# 1-Schematic_Tutorial_PJ.net
KiCad netlist of a schematic drawn in EasyEDA
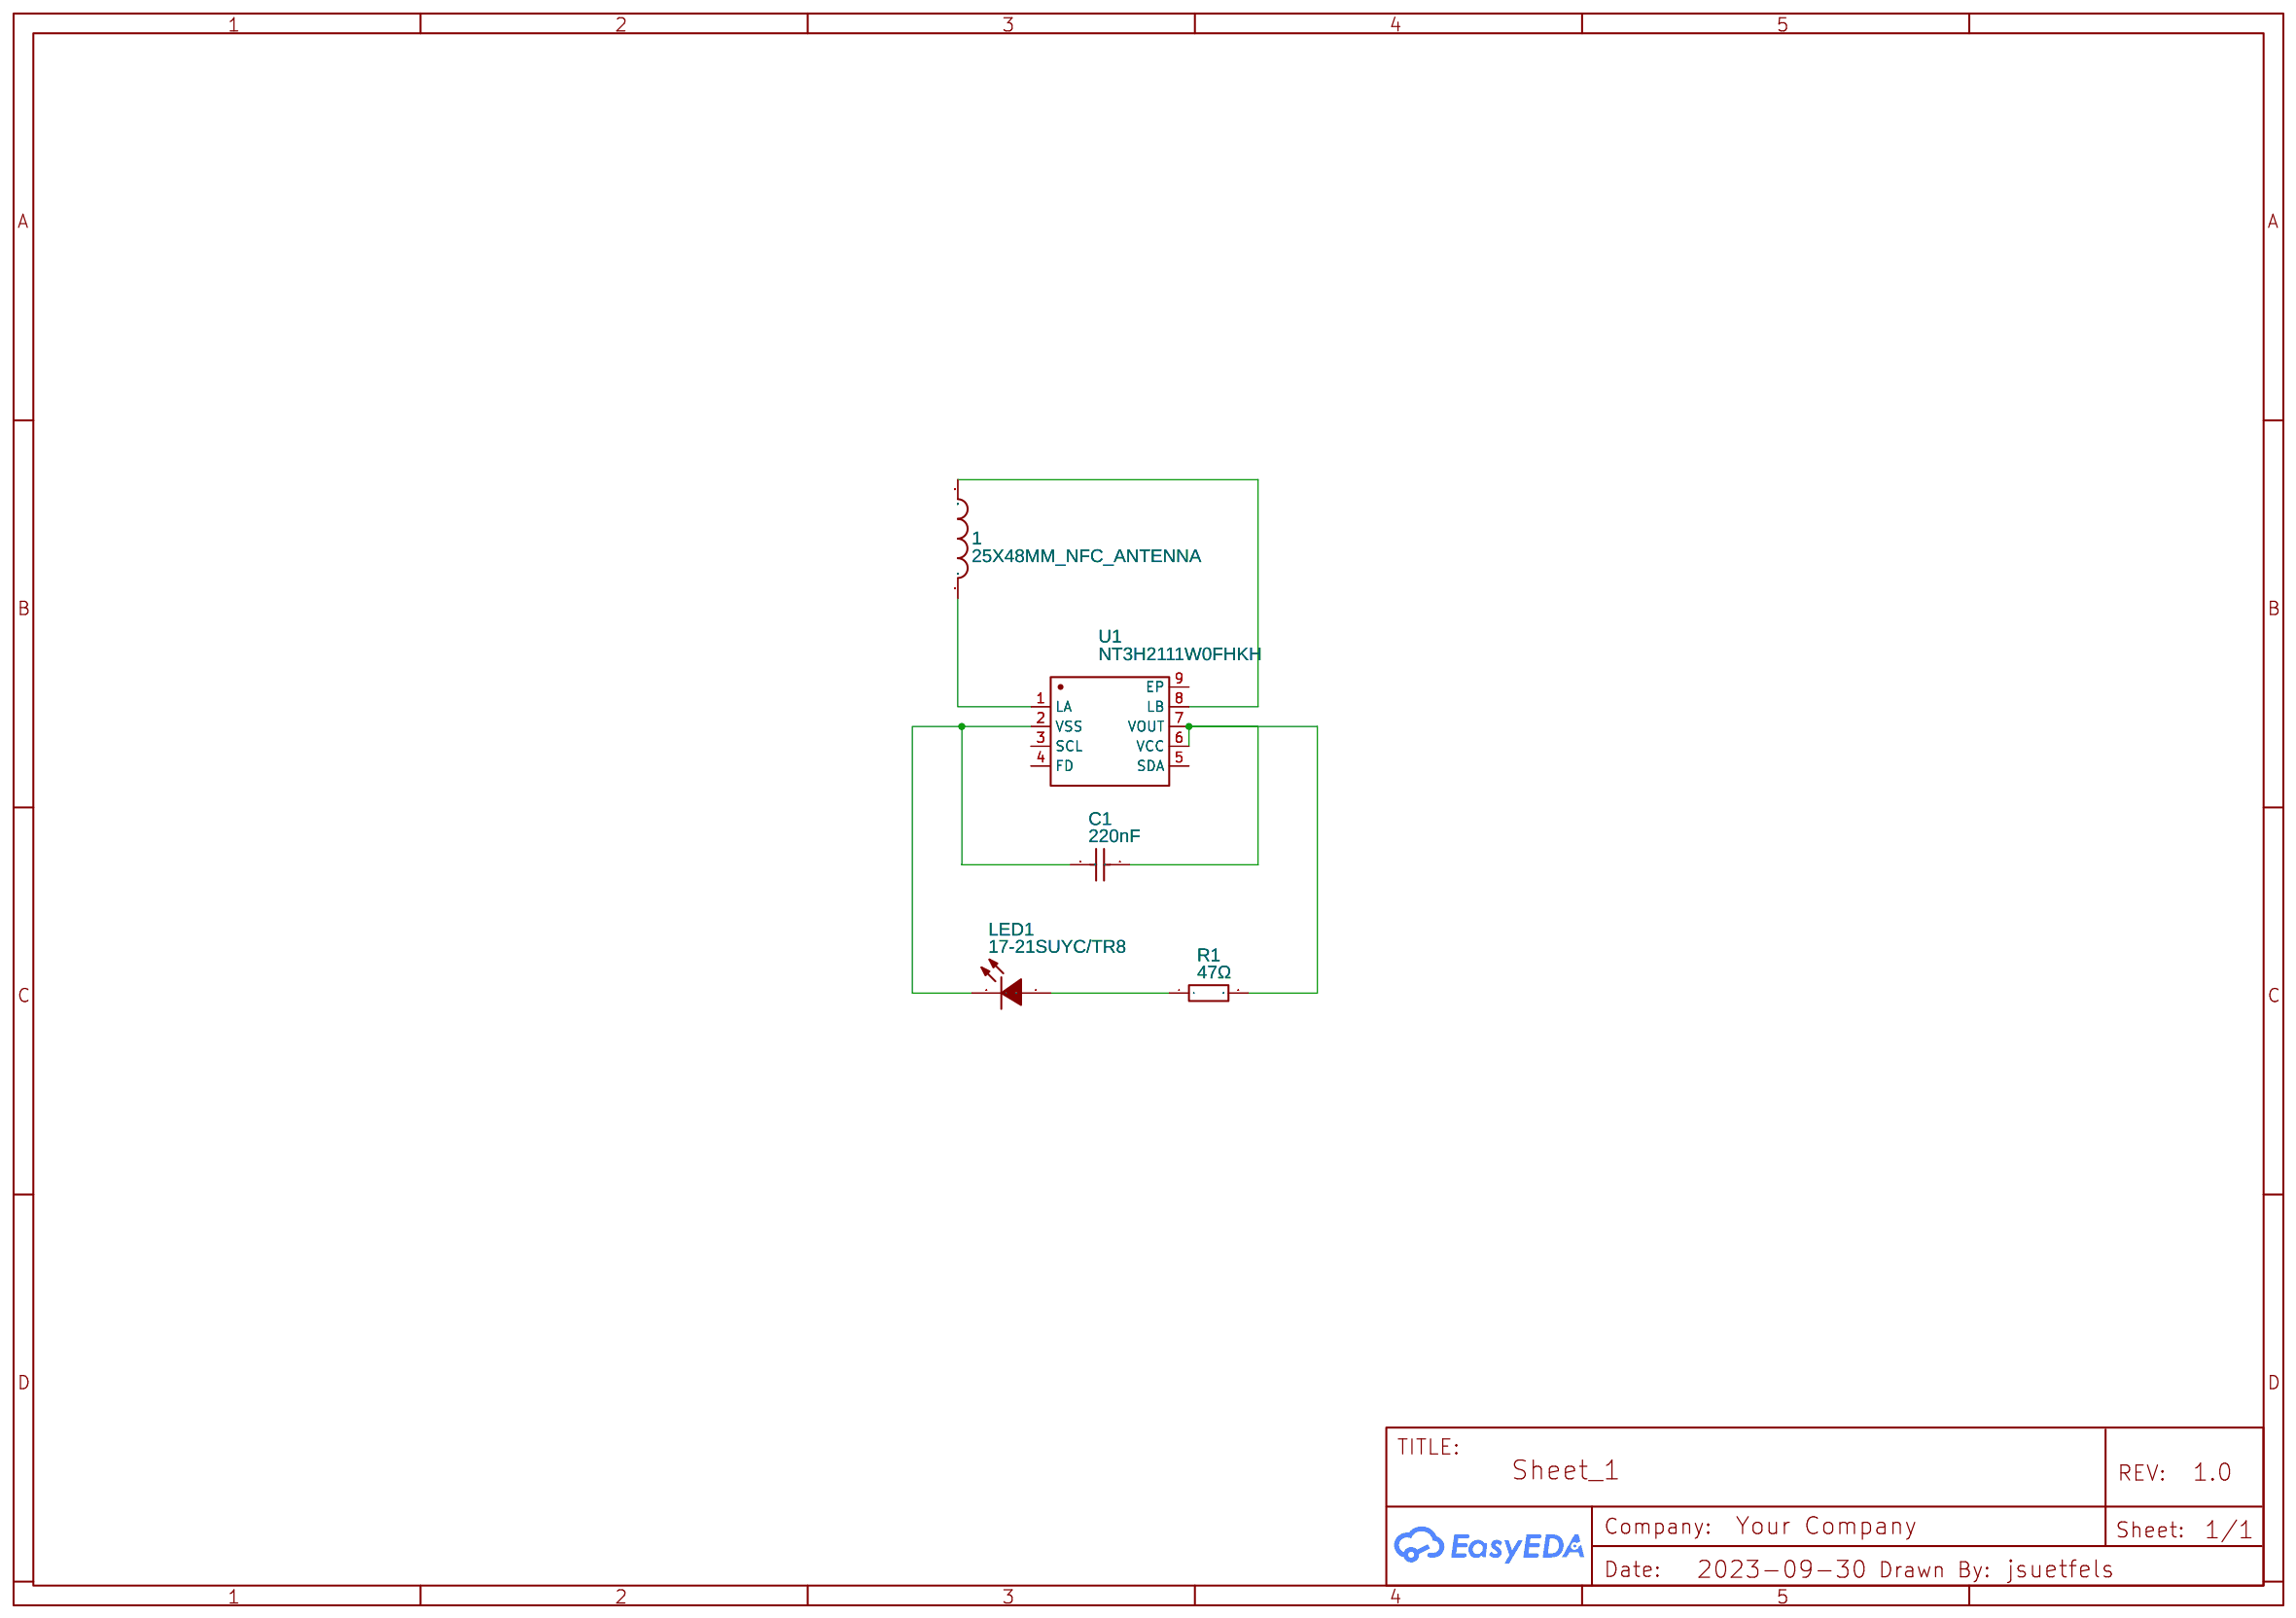
[diagram p0: schematic sheet]

(export (version "E")
  (design (tool "Eeschema 10.0.6"))
  (components
    (comp (ref "1") (value "25X48MM_NFC_ANTENNA") (libsource (lib "") (part "25X48MM_NFC_ANTENNA")))
    (comp (ref "C1")
      (value "220nF")
      (fields
        (field (name "Manufacturer Part") "CL10B224KA8NNNC")
        (field (name "Manufacturer") "SAMSUNG(三星)")
      )
      (libsource (lib "") (part "CL10B224KA8NNNC"))
    )
    (comp (ref "LED1")
      (value "17-21SUYC/TR8")
      (fields (field (name "Manufacturer Part") "KT-0805黄灯") (field (name "Manufacturer") "KENTO"))
      (libsource (lib "") (part "17-21SUYC/TR8"))
    )
    (comp (ref "R1")
      (value "47Ω")
      (fields
        (field (name "Manufacturer Part") "0603WAF470JT5E")
        (field (name "Manufacturer") "UNI-ROYAL(厚声)")
      )
      (libsource (lib "") (part "0603WAF470JT5E"))
    )
    (comp (ref "U1")
      (value "NT3H2111W0FHKH")
      (fields (field (name "Manufacturer") "NXP(恩智浦)"))
      (libsource (lib "") (part "NT3H2111W0FHKH"))
    )
  )
  (nets
    (net (code "1") (name "Net-(LED1-+)") (class "Default")
      (node (ref "LED1") (pin "1") (pinfunction "+_1") (pintype "unspecified"))
      (node (ref "R1") (pin "1") (pinfunction "1_1") (pintype "input"))
    )
    (net (code "2") (name "Net-(LED1--)") (class "Default")
      (node (ref "C1") (pin "1") (pinfunction "1_1") (pintype "input"))
      (node (ref "LED1") (pin "2") (pinfunction "-_2") (pintype "unspecified"))
      (node (ref "U1") (pin "2") (pinfunction "VSS_2") (pintype "unspecified"))
    )
    (net (code "3") (name "Net-(U1-LA)") (class "Default")
      (node (ref "1") (pin "P$2") (pinfunction "P$2_P$2") (pintype "bidirectional"))
      (node (ref "U1") (pin "1") (pinfunction "LA_1") (pintype "unspecified"))
    )
    (net (code "4") (name "Net-(U1-LB)") (class "Default")
      (node (ref "1") (pin "P$1") (pinfunction "P$1_P$1") (pintype "bidirectional"))
      (node (ref "U1") (pin "8") (pinfunction "LB_8") (pintype "unspecified"))
    )
    (net (code "5") (name "Net-(U1-VCC)") (class "Default")
      (node (ref "C1") (pin "2") (pinfunction "2_2") (pintype "input"))
      (node (ref "R1") (pin "2") (pinfunction "2_2") (pintype "input"))
      (node (ref "U1") (pin "6") (pinfunction "VCC_6") (pintype "unspecified"))
      (node (ref "U1") (pin "7") (pinfunction "VOUT_7") (pintype "unspecified"))
    )
    (net (code "6") (name "unconnected-(U1-EP-Pad9)") (class "Default")
      (node (ref "U1") (pin "9") (pinfunction "EP_9") (pintype "unspecified"))
    )
    (net (code "7") (name "unconnected-(U1-FD-Pad4)") (class "Default")
      (node (ref "U1") (pin "4") (pinfunction "FD_4") (pintype "unspecified"))
    )
    (net (code "8") (name "unconnected-(U1-SCL-Pad3)") (class "Default")
      (node (ref "U1") (pin "3") (pinfunction "SCL_3") (pintype "unspecified"))
    )
    (net (code "9") (name "unconnected-(U1-SDA-Pad5)") (class "Default")
      (node (ref "U1") (pin "5") (pinfunction "SDA_5") (pintype "unspecified"))
    )
  )
)
